# CYAN_EVSE_Power_board_v1_1.net
KiCad netlist of a schematic drawn in Altium Designer
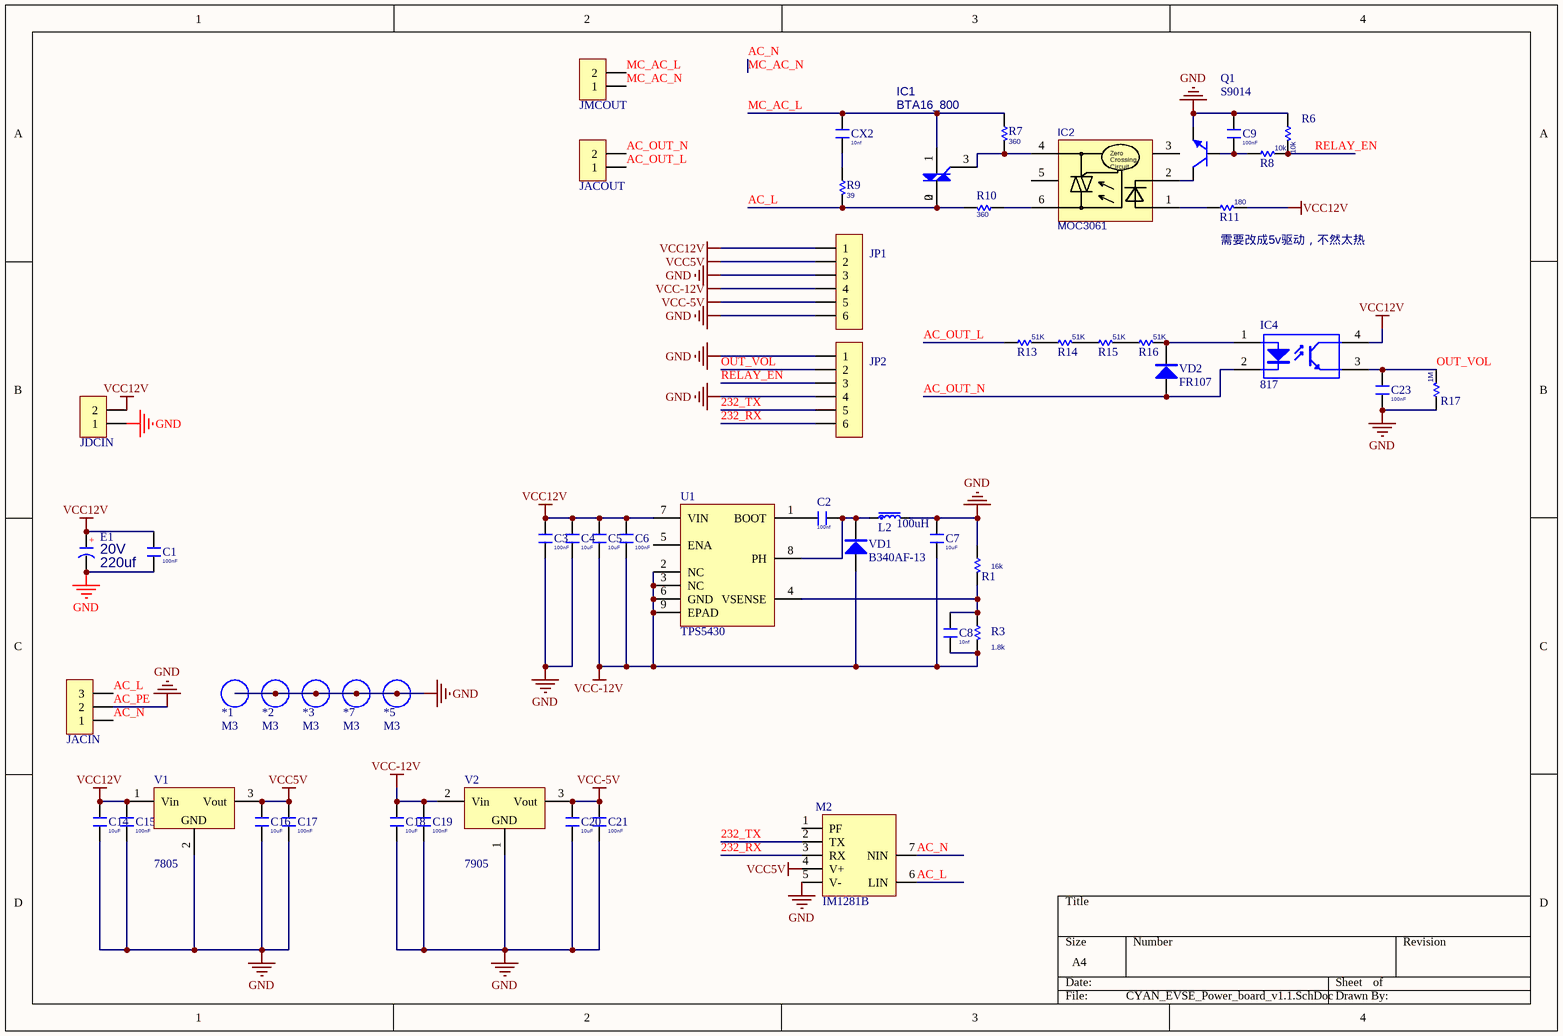
[diagram p0: CYAN_EVSE_Power_board_v1.1.SchDoc]

(export (version "E")
  (design (tool "Eeschema 10.0.6"))
  (components
    (comp (ref "*1")
      (value "M3")
      (footprint "M3 125X300")
      (description "铜柱孔")
      (libsource (lib "未分类器件") (part "M3"))
    )
    (comp (ref "*2")
      (value "M3")
      (footprint "M3 125X300")
      (description "铜柱孔")
      (libsource (lib "未分类器件") (part "M3"))
    )
    (comp (ref "*3")
      (value "M3")
      (footprint "M3 125X300")
      (description "铜柱孔")
      (libsource (lib "未分类器件") (part "M3"))
    )
    (comp (ref "*5")
      (value "M3")
      (footprint "M3 125X300")
      (description "铜柱孔")
      (libsource (lib "未分类器件") (part "M3"))
    )
    (comp (ref "*7")
      (value "M3")
      (footprint "M3 125X300")
      (description "铜柱孔")
      (libsource (lib "未分类器件") (part "M3"))
    )
    (comp (ref "C1")
      (value "100nF")
      (footprint "C 0805")
      (description "无极性贴片电容")
      (fields (field (name "VOLTAGE") "25V") (field (name "Comment") "C"))
      (libsource (lib "电阻-电容-电感") (part "C"))
    )
    (comp (ref "C2")
      (value "100nf")
      (footprint "C 0805")
      (description "无极性贴片电容")
      (fields (field (name "VOLTAGE") "50V") (field (name "Comment") "C"))
      (libsource (lib "电阻-电容-电感") (part "C"))
    )
    (comp (ref "C3")
      (value "100nF")
      (footprint "C 0805")
      (description "无极性贴片电容")
      (fields (field (name "VOLTAGE") "50V") (field (name "Comment") "C"))
      (libsource (lib "电阻-电容-电感") (part "C"))
    )
    (comp (ref "C4")
      (value "10uF")
      (footprint "C 0805")
      (description "无极性贴片电容")
      (fields (field (name "VOLTAGE") "50V") (field (name "Comment") "C"))
      (libsource (lib "电阻-电容-电感") (part "C"))
    )
    (comp (ref "C5")
      (value "10uF")
      (footprint "C 0805")
      (description "无极性贴片电容")
      (fields (field (name "VOLTAGE") "50V") (field (name "Comment") "C"))
      (libsource (lib "电阻-电容-电感") (part "C"))
    )
    (comp (ref "C6")
      (value "100nF")
      (footprint "C 0805")
      (description "无极性贴片电容")
      (fields (field (name "VOLTAGE") "50V") (field (name "Comment") "C"))
      (libsource (lib "电阻-电容-电感") (part "C"))
    )
    (comp (ref "C7")
      (value "10uF")
      (footprint "C 0805")
      (description "无极性贴片电容")
      (fields (field (name "VOLTAGE") "25V") (field (name "Comment") "C"))
      (libsource (lib "电阻-电容-电感") (part "C"))
    )
    (comp (ref "C8")
      (value "10nf")
      (footprint "C 0805")
      (description "无极性贴片电容")
      (fields (field (name "VOLTAGE") "50V") (field (name "Comment") "C"))
      (libsource (lib "电阻-电容-电感") (part "C"))
    )
    (comp (ref "C9")
      (value "100nF")
      (footprint "C 0805")
      (description "无极性贴片电容")
      (fields (field (name "VOLTAGE") "20V") (field (name "Comment") "C"))
      (libsource (lib "电阻-电容-电感") (part "C"))
    )
    (comp (ref "C14")
      (value "10uF")
      (footprint "C 0805")
      (description "无极性贴片电容")
      (fields (field (name "VOLTAGE") "50V") (field (name "Comment") "C"))
      (libsource (lib "电阻-电容-电感") (part "C"))
    )
    (comp (ref "C15")
      (value "100nF")
      (footprint "C 0805")
      (description "无极性贴片电容")
      (fields (field (name "VOLTAGE") "50V") (field (name "Comment") "C"))
      (libsource (lib "电阻-电容-电感") (part "C"))
    )
    (comp (ref "C16")
      (value "10uF")
      (footprint "C 0805")
      (description "无极性贴片电容")
      (fields (field (name "VOLTAGE") "50V") (field (name "Comment") "C"))
      (libsource (lib "电阻-电容-电感") (part "C"))
    )
    (comp (ref "C17")
      (value "100nF")
      (footprint "C 0805")
      (description "无极性贴片电容")
      (fields (field (name "VOLTAGE") "50V") (field (name "Comment") "C"))
      (libsource (lib "电阻-电容-电感") (part "C"))
    )
    (comp (ref "C18")
      (value "10uF")
      (footprint "C 0805")
      (description "无极性贴片电容")
      (fields (field (name "VOLTAGE") "50V") (field (name "Comment") "C"))
      (libsource (lib "电阻-电容-电感") (part "C"))
    )
    (comp (ref "C19")
      (value "100nF")
      (footprint "C 0805")
      (description "无极性贴片电容")
      (fields (field (name "VOLTAGE") "50V") (field (name "Comment") "C"))
      (libsource (lib "电阻-电容-电感") (part "C"))
    )
    (comp (ref "C20")
      (value "10uF")
      (footprint "C 0805")
      (description "无极性贴片电容")
      (fields (field (name "VOLTAGE") "50V") (field (name "Comment") "C"))
      (libsource (lib "电阻-电容-电感") (part "C"))
    )
    (comp (ref "C21")
      (value "100nF")
      (footprint "C 0805")
      (description "无极性贴片电容")
      (fields (field (name "VOLTAGE") "50V") (field (name "Comment") "C"))
      (libsource (lib "电阻-电容-电感") (part "C"))
    )
    (comp (ref "C23")
      (value "100nF")
      (footprint "C 0805")
      (description "无极性贴片电容")
      (fields (field (name "VOLTAGE") "20V") (field (name "Comment") "C"))
      (libsource (lib "电阻-电容-电感") (part "C"))
    )
    (comp (ref "CX2")
      (value "10nf")
      (footprint "CX 10*13*11")
      (description "X电容")
      (fields (field (name "VOLTAGE") "440V") (field (name "Comment") "X1 安规电容"))
      (libsource (lib "电阻-电容-电感") (part "C-CX"))
    )
    (comp (ref "E1")
      (value "220uf")
      (footprint "CM D(6.3*5.4)")
      (description "贴片电解电容")
      (fields (field (name "VOLTAGE") "20V") (field (name "Comment") "C-CM"))
      (libsource (lib "电阻-电容-电感") (part "C-CM"))
    )
    (comp (ref "IC1")
      (value "BTA16_800")
      (footprint "TO220B")
      (description "双向可控硅")
      (libsource (lib "场效应管-可控硅") (part "BTA12_600"))
    )
    (comp (ref "IC2")
      (value "MOC3061")
      (footprint "DIP6-300")
      (description "4(6)00v 带过0检测 光电可控硅 led电流15ma 1.3v")
      (fields (field (name "BOM_MANUFACTURER PART") "MOC3041M") (field (name "BOM_SUPPLIER PART") "C8921"))
      (libsource (lib "IC芯片") (part "MOC304(6)1"))
    )
    (comp (ref "IC4")
      (value "817")
      (footprint "SOP4-W2.54_M")
      (description "线性光耦")
      (libsource (lib "传感元件") (part "817"))
    )
    (comp (ref "JACIN")
      (value "HDR-1X3")
      (footprint "KF2EDGK5.0-3P_H")
      (description "3P接插件")
      (libsource (lib "接插件") (part "Header 3"))
    )
    (comp (ref "JACOUT")
      (value "HDR-1X2")
      (footprint "MC 1,5/ 2-G-3,81")
      (description "2P接插件")
      (libsource (lib "接插件") (part "Header 2"))
    )
    (comp (ref "JDCIN")
      (value "HDR-1X2")
      (footprint "MC 1,5/ 2-G-3,81")
      (description "2P接插件")
      (libsource (lib "接插件") (part "Header 2"))
    )
    (comp (ref "JMCOUT")
      (value "HDR-1X2")
      (footprint "MC 1,5/ 2-G-3,81")
      (description "2P接插件")
      (libsource (lib "接插件") (part "Header 2"))
    )
    (comp (ref "JP1")
      (value "HDR-1X6")
      (footprint "XH2.54-6P")
      (description "6P接插件")
      (libsource (lib "接插件") (part "Header 6"))
    )
    (comp (ref "JP2")
      (value "HDR-1X6")
      (footprint "XH2.54-6P")
      (description "6P接插件")
      (libsource (lib "接插件") (part "Header 6"))
    )
    (comp (ref "L2")
      (value "100uH")
      (footprint "CD75")
      (description "贴片功率电感")
      (libsource (lib "电阻-电容-电感") (part "L-CD"))
    )
    (comp (ref "M2")
      (value "IM1281B")
      (footprint "IM1281B")
      (description "单相交流电能计量模块")
      (libsource (lib "模块") (part "IM1281B"))
    )
    (comp (ref "Q1")
      (value "S9014")
      (footprint "SOT23-3N")
      (description "低噪放大-NPN型")
      (libsource (lib "三极管") (part "9014-SMD"))
    )
    (comp (ref "R1")
      (value "16k")
      (footprint "R 0805")
      (description "贴片电阻")
      (fields (field (name "Comment") "R"))
      (libsource (lib "电阻-电容-电感") (part "R"))
    )
    (comp (ref "R3")
      (value "1.8k")
      (footprint "R 0805")
      (description "贴片电阻")
      (fields (field (name "Comment") "R"))
      (libsource (lib "电阻-电容-电感") (part "R"))
    )
    (comp (ref "R6")
      (value "10k")
      (footprint "R 0805")
      (description "贴片电阻")
      (fields (field (name "Comment") "R"))
      (libsource (lib "电阻-电容-电感") (part "R"))
    )
    (comp (ref "R7")
      (value "360")
      (footprint "RS 1/2W")
      (description "直插色环电阻")
      (fields (field (name "Comment") "R-CRR"))
      (libsource (lib "电阻-电容-电感") (part "R-CRR"))
    )
    (comp (ref "R8")
      (value "10k")
      (footprint "R 0805")
      (description "贴片电阻")
      (fields (field (name "Comment") "R"))
      (libsource (lib "电阻-电容-电感") (part "R"))
    )
    (comp (ref "R9")
      (value "39")
      (footprint "RS 2W")
      (description "直插色环电阻")
      (fields (field (name "Comment") "R-CRR"))
      (libsource (lib "电阻-电容-电感") (part "R-CRR"))
    )
    (comp (ref "R10")
      (value "360")
      (footprint "RS 1/2W")
      (description "直插色环电阻")
      (fields (field (name "Comment") "R-CRR"))
      (libsource (lib "电阻-电容-电感") (part "R-CRR"))
    )
    (comp (ref "R11")
      (value "180")
      (footprint "R 0805")
      (description "贴片电阻")
      (fields (field (name "Comment") "R"))
      (libsource (lib "电阻-电容-电感") (part "R"))
    )
    (comp (ref "R13")
      (value "51K")
      (footprint "R 1206")
      (description "贴片电阻")
      (fields (field (name "Comment") "R"))
      (libsource (lib "电阻-电容-电感") (part "R"))
    )
    (comp (ref "R14")
      (value "51K")
      (footprint "R 1206")
      (description "贴片电阻")
      (fields (field (name "Comment") "R"))
      (libsource (lib "电阻-电容-电感") (part "R"))
    )
    (comp (ref "R15")
      (value "51K")
      (footprint "R 1206")
      (description "贴片电阻")
      (fields (field (name "Comment") "R"))
      (libsource (lib "电阻-电容-电感") (part "R"))
    )
    (comp (ref "R16")
      (value "51K")
      (footprint "R 1206")
      (description "贴片电阻")
      (fields (field (name "Comment") "R"))
      (libsource (lib "电阻-电容-电感") (part "R"))
    )
    (comp (ref "R17")
      (value "1M")
      (footprint "R 0805")
      (description "贴片电阻")
      (fields (field (name "Comment") "R"))
      (libsource (lib "电阻-电容-电感") (part "R"))
    )
    (comp (ref "U1")
      (value "TPS5430")
      (footprint "SOP8_EPAD_VIA")
      (description "3A 36v buck控制器，内置fet")
      (libsource (lib "IC芯片") (part "TPS5430"))
    )
    (comp (ref "V1")
      (value "7805")
      (footprint "TO252")
      (description "线性稳压芯片")
      (libsource (lib "IC芯片") (part "78xx"))
    )
    (comp (ref "V2")
      (value "7905")
      (footprint "TO252")
      (description "线性稳压芯片")
      (libsource (lib "IC芯片") (part "79xx"))
    )
    (comp (ref "VD1")
      (value "B340AF-13")
      (footprint "SMA")
      (description "肖特基二极管")
      (libsource (lib "二极管-整流桥") (part "SS14"))
    )
    (comp (ref "VD2")
      (value "FR107")
      (footprint "SOD-123")
      (description "快恢复整流二极管")
      (libsource (lib "二极管-整流桥") (part "FR107"))
    )
  )
  (nets
    (net (code "1") (name "/232_RX") (class "Default")
      (node (ref "JP2") (pin "6") (pinfunction "6_6") (pintype "passive"))
      (node (ref "M2") (pin "3") (pinfunction "RX_3") (pintype "passive"))
    )
    (net (code "2") (name "/232_TX") (class "Default")
      (node (ref "JP2") (pin "5") (pinfunction "5_5") (pintype "passive"))
      (node (ref "M2") (pin "2") (pinfunction "TX_2") (pintype "passive"))
    )
    (net (code "3") (name "/AC_L") (class "Default")
      (node (ref "IC1") (pin "0") (pinfunction "18_0") (pintype "passive"))
      (node (ref "IC1") (pin "2") (pinfunction "A2_2") (pintype "passive"))
      (node (ref "JACIN") (pin "3") (pinfunction "3_3") (pintype "passive"))
      (node (ref "M2") (pin "6") (pinfunction "LIN_6") (pintype "passive"))
      (node (ref "R10") (pin "2") (pinfunction "2_2") (pintype "passive"))
      (node (ref "R9") (pin "2") (pinfunction "2_2") (pintype "passive"))
    )
    (net (code "4") (name "/AC_N") (class "Default")
      (node (ref "JACIN") (pin "1") (pinfunction "1_1") (pintype "passive"))
      (node (ref "JMCOUT") (pin "1") (pinfunction "1_1") (pintype "passive"))
      (node (ref "M2") (pin "7") (pinfunction "NIN_7") (pintype "passive"))
    )
    (net (code "5") (name "/AC_OUT_L") (class "Default")
      (node (ref "JACOUT") (pin "1") (pinfunction "1_1") (pintype "passive"))
      (node (ref "R13") (pin "1") (pinfunction "1_1") (pintype "passive"))
    )
    (net (code "6") (name "/AC_OUT_N") (class "Default")
      (node (ref "IC4") (pin "2") (pinfunction "K_2") (pintype "passive"))
      (node (ref "JACOUT") (pin "2") (pinfunction "2_2") (pintype "passive"))
      (node (ref "VD2") (pin "1") (pinfunction "A_1") (pintype "passive"))
    )
    (net (code "7") (name "/MC_AC_L") (class "Default")
      (node (ref "CX2") (pin "1") (pinfunction "1_1") (pintype "passive"))
      (node (ref "IC1") (pin "1") (pinfunction "A1_1") (pintype "passive"))
      (node (ref "JMCOUT") (pin "2") (pinfunction "2_2") (pintype "passive"))
      (node (ref "R7") (pin "1") (pinfunction "1_1") (pintype "passive"))
    )
    (net (code "8") (name "/OUT_VOL") (class "Default")
      (node (ref "C23") (pin "2") (pinfunction "2_2") (pintype "passive"))
      (node (ref "IC4") (pin "3") (pinfunction "E_3") (pintype "passive"))
      (node (ref "JP2") (pin "2") (pinfunction "2_2") (pintype "passive"))
      (node (ref "R17") (pin "2") (pinfunction "2_2") (pintype "passive"))
    )
    (net (code "9") (name "/RELAY_EN") (class "Default")
      (node (ref "JP2") (pin "3") (pinfunction "3_3") (pintype "passive"))
      (node (ref "R6") (pin "2") (pinfunction "2_2") (pintype "passive"))
      (node (ref "R8") (pin "2") (pinfunction "2_2") (pintype "passive"))
    )
    (net (code "10") (name "GND") (class "Default")
      (node (ref "*1") (pin "0") (pinfunction "0_0") (pintype "passive"))
      (node (ref "*2") (pin "0") (pinfunction "0_0") (pintype "passive"))
      (node (ref "*3") (pin "0") (pinfunction "0_0") (pintype "passive"))
      (node (ref "*5") (pin "0") (pinfunction "0_0") (pintype "passive"))
      (node (ref "*7") (pin "0") (pinfunction "0_0") (pintype "passive"))
      (node (ref "C1") (pin "1") (pinfunction "1_1") (pintype "passive"))
      (node (ref "C14") (pin "1") (pinfunction "1_1") (pintype "passive"))
      (node (ref "C15") (pin "1") (pinfunction "1_1") (pintype "passive"))
      (node (ref "C16") (pin "1") (pinfunction "1_1") (pintype "passive"))
      (node (ref "C17") (pin "1") (pinfunction "1_1") (pintype "passive"))
      (node (ref "C18") (pin "1") (pinfunction "1_1") (pintype "passive"))
      (node (ref "C19") (pin "1") (pinfunction "1_1") (pintype "passive"))
      (node (ref "C20") (pin "1") (pinfunction "1_1") (pintype "passive"))
      (node (ref "C21") (pin "1") (pinfunction "1_1") (pintype "passive"))
      (node (ref "C23") (pin "1") (pinfunction "1_1") (pintype "passive"))
      (node (ref "C3") (pin "1") (pinfunction "1_1") (pintype "passive"))
      (node (ref "C4") (pin "2") (pinfunction "2_2") (pintype "passive"))
      (node (ref "C7") (pin "2") (pinfunction "2_2") (pintype "passive"))
      (node (ref "C9") (pin "1") (pinfunction "1_1") (pintype "passive"))
      (node (ref "E1") (pin "2") (pinfunction "2_2") (pintype "passive"))
      (node (ref "JACIN") (pin "2") (pinfunction "2_2") (pintype "passive"))
      (node (ref "JDCIN") (pin "1") (pinfunction "1_1") (pintype "passive"))
      (node (ref "JP1") (pin "3") (pinfunction "3_3") (pintype "passive"))
      (node (ref "JP1") (pin "6") (pinfunction "6_6") (pintype "passive"))
      (node (ref "JP2") (pin "1") (pinfunction "1_1") (pintype "passive"))
      (node (ref "JP2") (pin "4") (pinfunction "4_4") (pintype "passive"))
      (node (ref "L2") (pin "2") (pinfunction "2_2") (pintype "passive"))
      (node (ref "M2") (pin "5") (pinfunction "V-_5") (pintype "passive"))
      (node (ref "Q1") (pin "2") (pinfunction "E_2") (pintype "passive"))
      (node (ref "R1") (pin "1") (pinfunction "1_1") (pintype "passive"))
      (node (ref "R17") (pin "1") (pinfunction "1_1") (pintype "passive"))
      (node (ref "R6") (pin "1") (pinfunction "1_1") (pintype "passive"))
      (node (ref "V1") (pin "2") (pinfunction "GND_2") (pintype "passive"))
      (node (ref "V2") (pin "1") (pinfunction "GND_1") (pintype "passive"))
    )
    (net (code "11") (name "Net-(CX2-Pad2)") (class "Default")
      (node (ref "CX2") (pin "2") (pinfunction "2_2") (pintype "passive"))
      (node (ref "R9") (pin "1") (pinfunction "1_1") (pintype "passive"))
    )
    (net (code "12") (name "Net-(IC1-G)") (class "Default")
      (node (ref "IC1") (pin "3") (pinfunction "G_3") (pintype "passive"))
      (node (ref "IC2") (pin "4") (pinfunction "T2_4") (pintype "passive"))
      (node (ref "R7") (pin "2") (pinfunction "2_2") (pintype "passive"))
    )
    (net (code "13") (name "Net-(IC2-A)") (class "Default")
      (node (ref "IC2") (pin "1") (pinfunction "A_1") (pintype "passive"))
      (node (ref "R11") (pin "1") (pinfunction "1_1") (pintype "passive"))
    )
    (net (code "14") (name "Net-(IC2-K)") (class "Default")
      (node (ref "IC2") (pin "2") (pinfunction "K_2") (pintype "passive"))
      (node (ref "Q1") (pin "3") (pinfunction "C_3") (pintype "passive"))
    )
    (net (code "15") (name "Net-(IC2-T1)") (class "Default")
      (node (ref "IC2") (pin "6") (pinfunction "T1_6") (pintype "passive"))
      (node (ref "R10") (pin "1") (pinfunction "1_1") (pintype "passive"))
    )
    (net (code "16") (name "Net-(IC4-A)") (class "Default")
      (node (ref "IC4") (pin "1") (pinfunction "A_1") (pintype "passive"))
      (node (ref "R16") (pin "2") (pinfunction "2_2") (pintype "passive"))
      (node (ref "VD2") (pin "2") (pinfunction "K_2") (pintype "passive"))
    )
    (net (code "17") (name "Net-(Q1-B)") (class "Default")
      (node (ref "C9") (pin "2") (pinfunction "2_2") (pintype "passive"))
      (node (ref "Q1") (pin "1") (pinfunction "B_1") (pintype "passive"))
      (node (ref "R8") (pin "1") (pinfunction "1_1") (pintype "passive"))
    )
    (net (code "18") (name "Net-(R13-Pad2)") (class "Default")
      (node (ref "R13") (pin "2") (pinfunction "2_2") (pintype "passive"))
      (node (ref "R14") (pin "1") (pinfunction "1_1") (pintype "passive"))
    )
    (net (code "19") (name "Net-(R14-Pad2)") (class "Default")
      (node (ref "R14") (pin "2") (pinfunction "2_2") (pintype "passive"))
      (node (ref "R15") (pin "1") (pinfunction "1_1") (pintype "passive"))
    )
    (net (code "20") (name "Net-(R15-Pad2)") (class "Default")
      (node (ref "R15") (pin "2") (pinfunction "2_2") (pintype "passive"))
      (node (ref "R16") (pin "1") (pinfunction "1_1") (pintype "passive"))
    )
    (net (code "21") (name "Net-(U1-BOOT)") (class "Default")
      (node (ref "C2") (pin "1") (pinfunction "1_1") (pintype "passive"))
      (node (ref "U1") (pin "1") (pinfunction "BOOT_1") (pintype "passive"))
    )
    (net (code "22") (name "Net-(U1-PH)") (class "Default")
      (node (ref "C2") (pin "2") (pinfunction "2_2") (pintype "passive"))
      (node (ref "L2") (pin "1") (pinfunction "1_1") (pintype "passive"))
      (node (ref "U1") (pin "8") (pinfunction "PH_8") (pintype "passive"))
      (node (ref "VD1") (pin "2") (pinfunction "K_2") (pintype "passive"))
    )
    (net (code "23") (name "Net-(U1-VSENSE)") (class "Default")
      (node (ref "C8") (pin "1") (pinfunction "1_1") (pintype "passive"))
      (node (ref "R1") (pin "2") (pinfunction "2_2") (pintype "passive"))
      (node (ref "R3") (pin "1") (pinfunction "1_1") (pintype "passive"))
      (node (ref "U1") (pin "4") (pinfunction "VSENSE_4") (pintype "passive"))
    )
    (net (code "24") (name "VCC-5V") (class "Default")
      (node (ref "C20") (pin "2") (pinfunction "2_2") (pintype "passive"))
      (node (ref "C21") (pin "2") (pinfunction "2_2") (pintype "passive"))
      (node (ref "JP1") (pin "5") (pinfunction "5_5") (pintype "passive"))
      (node (ref "V2") (pin "3") (pinfunction "Vout_3") (pintype "passive"))
    )
    (net (code "25") (name "VCC-12V") (class "Default")
      (node (ref "C18") (pin "2") (pinfunction "2_2") (pintype "passive"))
      (node (ref "C19") (pin "2") (pinfunction "2_2") (pintype "passive"))
      (node (ref "C5") (pin "1") (pinfunction "1_1") (pintype "passive"))
      (node (ref "C6") (pin "1") (pinfunction "1_1") (pintype "passive"))
      (node (ref "C7") (pin "1") (pinfunction "1_1") (pintype "passive"))
      (node (ref "C8") (pin "2") (pinfunction "2_2") (pintype "passive"))
      (node (ref "JP1") (pin "4") (pinfunction "4_4") (pintype "passive"))
      (node (ref "R3") (pin "2") (pinfunction "2_2") (pintype "passive"))
      (node (ref "U1") (pin "2") (pinfunction "NC_2") (pintype "passive"))
      (node (ref "U1") (pin "3") (pinfunction "NC_3") (pintype "passive"))
      (node (ref "U1") (pin "6") (pinfunction "GND_6") (pintype "passive"))
      (node (ref "U1") (pin "9") (pinfunction "EPAD_9") (pintype "passive"))
      (node (ref "V2") (pin "2") (pinfunction "Vin_2") (pintype "passive"))
      (node (ref "VD1") (pin "1") (pinfunction "A_1") (pintype "passive"))
    )
    (net (code "26") (name "VCC5V") (class "Default")
      (node (ref "C16") (pin "2") (pinfunction "2_2") (pintype "passive"))
      (node (ref "C17") (pin "2") (pinfunction "2_2") (pintype "passive"))
      (node (ref "JP1") (pin "2") (pinfunction "2_2") (pintype "passive"))
      (node (ref "M2") (pin "4") (pinfunction "V+_4") (pintype "passive"))
      (node (ref "V1") (pin "3") (pinfunction "Vout_3") (pintype "passive"))
    )
    (net (code "27") (name "VCC12V") (class "Default")
      (node (ref "C1") (pin "2") (pinfunction "2_2") (pintype "passive"))
      (node (ref "C14") (pin "2") (pinfunction "2_2") (pintype "passive"))
      (node (ref "C15") (pin "2") (pinfunction "2_2") (pintype "passive"))
      (node (ref "C3") (pin "2") (pinfunction "2_2") (pintype "passive"))
      (node (ref "C4") (pin "1") (pinfunction "1_1") (pintype "passive"))
      (node (ref "C5") (pin "2") (pinfunction "2_2") (pintype "passive"))
      (node (ref "C6") (pin "2") (pinfunction "2_2") (pintype "passive"))
      (node (ref "E1") (pin "1") (pinfunction "1_1") (pintype "passive"))
      (node (ref "IC4") (pin "4") (pinfunction "C_4") (pintype "passive"))
      (node (ref "JDCIN") (pin "2") (pinfunction "2_2") (pintype "passive"))
      (node (ref "JP1") (pin "1") (pinfunction "1_1") (pintype "passive"))
      (node (ref "R11") (pin "2") (pinfunction "2_2") (pintype "passive"))
      (node (ref "U1") (pin "7") (pinfunction "VIN_7") (pintype "passive"))
      (node (ref "V1") (pin "1") (pinfunction "Vin_1") (pintype "passive"))
    )
    (net (code "28") (name "unconnected-(IC2-NC-Pad3)") (class "Default")
      (node (ref "IC2") (pin "3") (pinfunction "NC_3") (pintype "passive"))
    )
    (net (code "29") (name "unconnected-(IC2-NC-Pad5)") (class "Default")
      (node (ref "IC2") (pin "5") (pinfunction "NC_5") (pintype "passive"))
    )
    (net (code "30") (name "unconnected-(M2-PF-Pad1)") (class "Default")
      (node (ref "M2") (pin "1") (pinfunction "PF_1") (pintype "passive"))
    )
    (net (code "31") (name "unconnected-(U1-ENA-Pad5)") (class "Default")
      (node (ref "U1") (pin "5") (pinfunction "ENA_5") (pintype "passive"))
    )
  )
)
